# PhatStats_Slim_Enclosure_ESP_PCB_v0_96.net
KiCad netlist of a schematic drawn in EAGLE
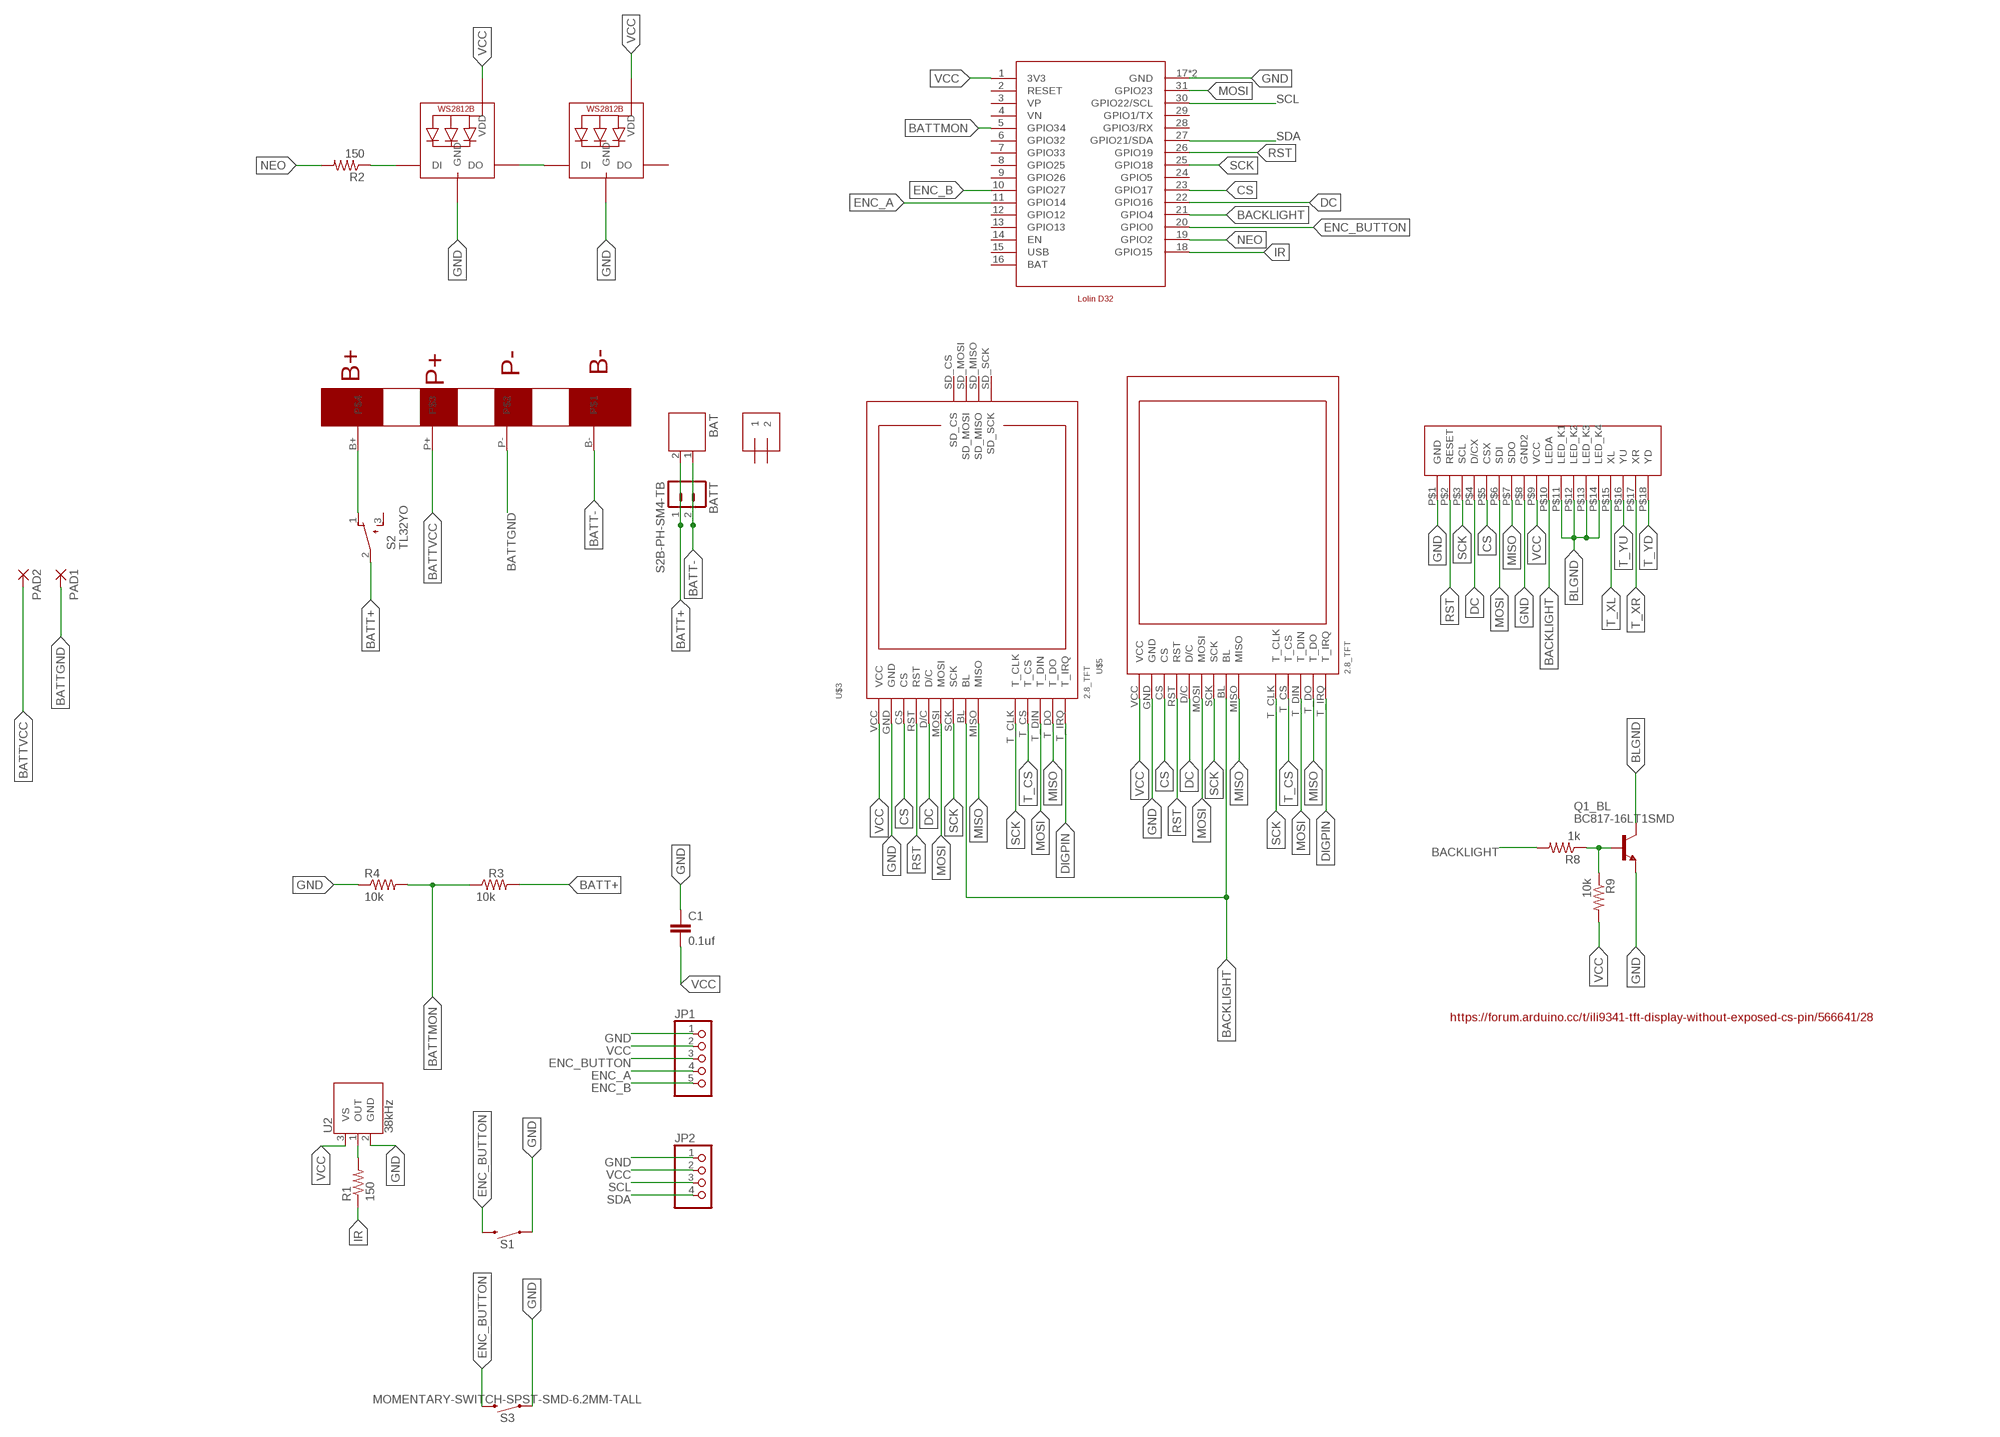
[diagram p0: schematic, sheet 1]

(export (version "E")
  (design (tool "Eeschema 10.0.6"))
  (components
    (comp (ref "0")
      (value "ILI9341-2.8")
      (footprint "eagle-import:ILI9341-2.8")
      (libsource (lib "eagle-import") (part "ILI9341-2.8"))
    )
    (comp (ref "BAT")
      (value "JST-PH2")
      (footprint "eagle-import:JST-PH2")
      (libsource (lib "eagle-import") (part "JST-PH2"))
    )
    (comp (ref "BATT")
      (value "S2B-PH-SM4-TB")
      (footprint "eagle-import:S2B-PH-SM4-TB")
      (libsource (lib "eagle-import") (part "S2B-PH-SM4-TB"))
    )
    (comp (ref "BMS")
      (value "DW01BATTERYPROT")
      (footprint "eagle-import:DW01BATTERYPROT")
      (libsource (lib "eagle-import") (part "DW01BATTERYPROT"))
    )
    (comp (ref "C1")
      (value "0.1uf")
      (footprint "eagle-import:C1206")
      (libsource (lib "eagle-import") (part "C-EUC1206"))
    )
    (comp (ref "J1")
      (value "1X2-3.5MM")
      (footprint "eagle-import:1X2-3.5MM")
      (libsource (lib "eagle-import") (part "1X2-3.5MM"))
    )
    (comp (ref "JP1")
      (value "PINHD-1X5")
      (footprint "eagle-import:1X05")
      (libsource (lib "eagle-import") (part "PINHD-1X5"))
    )
    (comp (ref "JP2")
      (value "PINHD-1X4")
      (footprint "eagle-import:1X04")
      (libsource (lib "eagle-import") (part "PINHD-1X4"))
    )
    (comp (ref "NEO1")
      (value "WS2812B5050")
      (footprint "eagle-import:WS2812B")
      (libsource (lib "eagle-import") (part "WS2812B5050"))
    )
    (comp (ref "NEO2")
      (value "WS2812B5050")
      (footprint "eagle-import:WS2812B")
      (libsource (lib "eagle-import") (part "WS2812B5050"))
    )
    (comp (ref "PAD1")
      (value "WIREPADSMD5-1,8")
      (footprint "eagle-import:5-1,8")
      (libsource (lib "eagle-import") (part "WIREPADSMD5-1,8"))
    )
    (comp (ref "PAD2")
      (value "WIREPADSMD5-1,8")
      (footprint "eagle-import:5-1,8")
      (libsource (lib "eagle-import") (part "WIREPADSMD5-1,8"))
    )
    (comp (ref "Q1_BL")
      (value "BC817-16LT1SMD")
      (footprint "eagle-import:SOT23-BEC")
      (libsource (lib "eagle-import") (part "BC817SMD-16LT1"))
    )
    (comp (ref "R1")
      (value "150")
      (footprint "eagle-import:M1206")
      (libsource (lib "eagle-import") (part "R-US_M1206"))
    )
    (comp (ref "R2")
      (value "150")
      (footprint "eagle-import:M1206")
      (libsource (lib "eagle-import") (part "R-US_M1206"))
    )
    (comp (ref "R3")
      (value "10k")
      (footprint "eagle-import:M1206")
      (libsource (lib "eagle-import") (part "R-US_M1206"))
    )
    (comp (ref "R4")
      (value "10k")
      (footprint "eagle-import:M1206")
      (libsource (lib "eagle-import") (part "R-US_M1206"))
    )
    (comp (ref "R8")
      (value "1k")
      (footprint "eagle-import:M1206")
      (libsource (lib "eagle-import") (part "R-US_M1206"))
    )
    (comp (ref "R9")
      (value "10k")
      (footprint "eagle-import:M1206")
      (libsource (lib "eagle-import") (part "R-US_M1206"))
    )
    (comp (ref "S1")
      (value "MOMENTARY-SWITCH-SPST-PTH-6.0MM")
      (footprint "eagle-import:TACTILE_SWITCH_PTH_6.0MM")
      (libsource (lib "eagle-import") (part "MOMENTARY-SWITCH-SPST-PTH-6.0MM"))
    )
    (comp (ref "S2")
      (value "TL32YO")
      (footprint "eagle-import:TL3XYO")
      (libsource (lib "eagle-import") (part "TL32YO"))
    )
    (comp (ref "S3")
      (value "MOMENTARY-SWITCH-SPST-SMD-6.2MM-TALL")
      (footprint "eagle-import:TACTILE_SWITCH_SMD_6.2MM_TALL")
      (libsource (lib "eagle-import") (part "MOMENTARY-SWITCH-SPST-SMD-6.2MM-TALL"))
    )
    (comp (ref "U$2")
      (value "LOLIND32")
      (footprint "eagle-import:LOLIND32")
      (libsource (lib "eagle-import") (part "LOLIND32"))
    )
    (comp (ref "U$3")
      (value "2.8_TFT")
      (footprint "eagle-import:2.8_TFT")
      (libsource (lib "eagle-import") (part "2.8_TFT"))
    )
    (comp (ref "U$5")
      (value "2.8_TFT")
      (footprint "eagle-import:2.8_TFT")
      (libsource (lib "eagle-import") (part "TML_ili9341-2.8_tft-display_PinHeader only_2.8_TFT"))
    )
    (comp (ref "U2")
      (value "38kHz")
      (footprint "eagle-import:TSOP382")
      (libsource (lib "eagle-import") (part "TSOP38238"))
    )
  )
  (nets
    (net (code "1") (name "/BAT") (class "Default")
      (node (ref "U$2") (pin "16") (pinfunction "BAT_16") (pintype "power_in"))
    )
    (net (code "2") (name "/SCL") (class "Default")
      (node (ref "JP2") (pin "3") (pinfunction "3_3") (pintype "passive"))
      (node (ref "U$2") (pin "30") (pinfunction "GPIO22/SCL_30") (pintype "bidirectional"))
    )
    (net (code "3") (name "/SDA") (class "Default")
      (node (ref "JP2") (pin "4") (pinfunction "4_4") (pintype "passive"))
      (node (ref "U$2") (pin "27") (pinfunction "GPIO21/SDA_27") (pintype "bidirectional"))
    )
    (net (code "4") (name "/USB") (class "Default")
      (node (ref "U$2") (pin "15") (pinfunction "USB_15") (pintype "power_in"))
    )
    (net (code "5") (name "BACKLIGHT") (class "Default")
      (node (ref "0") (pin "P$10") (pinfunction "LEDA_P$10") (pintype "bidirectional"))
      (node (ref "R8") (pin "2") (pinfunction "2_2") (pintype "passive"))
      (node (ref "U$2") (pin "21") (pinfunction "GPIO4_21") (pintype "bidirectional"))
      (node (ref "U$3") (pin "BL") (pinfunction "BL_BL") (pintype "bidirectional"))
      (node (ref "U$5") (pin "BL") (pinfunction "BL_BL") (pintype "bidirectional"))
    )
    (net (code "6") (name "BATT+") (class "Default")
      (node (ref "BAT") (pin "2") (pinfunction "2_2") (pintype "passive"))
      (node (ref "BATT") (pin "1") (pinfunction "1_1") (pintype "passive"))
      (node (ref "R3") (pin "2") (pinfunction "2_2") (pintype "passive"))
      (node (ref "S2") (pin "2") (pinfunction "P_2") (pintype "passive"))
    )
    (net (code "7") (name "BATT-") (class "Default")
      (node (ref "BAT") (pin "1") (pinfunction "1_1") (pintype "passive"))
      (node (ref "BATT") (pin "2") (pinfunction "2_2") (pintype "passive"))
      (node (ref "BMS") (pin "B-") (pinfunction "P$1_B-") (pintype "bidirectional"))
    )
    (net (code "8") (name "BATTGND") (class "Default")
      (node (ref "BMS") (pin "P-") (pinfunction "P$2_P-") (pintype "bidirectional"))
      (node (ref "PAD1") (pin "1") (pinfunction "P_1") (pintype "passive"))
    )
    (net (code "9") (name "BATTMON") (class "Default")
      (node (ref "R3") (pin "1") (pinfunction "1_1") (pintype "passive"))
      (node (ref "R4") (pin "2") (pinfunction "2_2") (pintype "passive"))
      (node (ref "U$2") (pin "5") (pinfunction "GPIO34_5") (pintype "input"))
    )
    (net (code "10") (name "BATTVCC") (class "Default")
      (node (ref "BMS") (pin "P+") (pinfunction "P$3_P+") (pintype "bidirectional"))
      (node (ref "PAD2") (pin "1") (pinfunction "P_1") (pintype "passive"))
    )
    (net (code "11") (name "BLGND") (class "Default")
      (node (ref "0") (pin "P$11") (pinfunction "LED_K1_P$11") (pintype "bidirectional"))
      (node (ref "0") (pin "P$12") (pinfunction "LED_K2_P$12") (pintype "bidirectional"))
      (node (ref "0") (pin "P$13") (pinfunction "LED_K3_P$13") (pintype "bidirectional"))
      (node (ref "0") (pin "P$14") (pinfunction "LED_K4_P$14") (pintype "bidirectional"))
      (node (ref "Q1_BL") (pin "C") (pinfunction "C_C") (pintype "passive"))
    )
    (net (code "12") (name "CS") (class "Default")
      (node (ref "0") (pin "P$5") (pinfunction "CSX_P$5") (pintype "bidirectional"))
      (node (ref "U$2") (pin "23") (pinfunction "GPIO17_23") (pintype "bidirectional"))
      (node (ref "U$3") (pin "CS") (pinfunction "CS_CS") (pintype "bidirectional"))
      (node (ref "U$5") (pin "CS") (pinfunction "CS_CS") (pintype "bidirectional"))
    )
    (net (code "13") (name "DC") (class "Default")
      (node (ref "0") (pin "P$4") (pinfunction "D/CX_P$4") (pintype "bidirectional"))
      (node (ref "U$2") (pin "22") (pinfunction "GPIO16_22") (pintype "bidirectional"))
      (node (ref "U$3") (pin "D/C") (pinfunction "D/C_D/C") (pintype "bidirectional"))
      (node (ref "U$5") (pin "D/C") (pinfunction "D/C_D/C") (pintype "bidirectional"))
    )
    (net (code "14") (name "DIGPIN") (class "Default")
      (node (ref "U$3") (pin "T_IRQ") (pinfunction "T_IRQ_T_IRQ") (pintype "bidirectional"))
      (node (ref "U$5") (pin "T_IRQ") (pinfunction "T_IRQ_T_IRQ") (pintype "bidirectional"))
    )
    (net (code "15") (name "ENC_A") (class "Default")
      (node (ref "JP1") (pin "4") (pinfunction "4_4") (pintype "passive"))
      (node (ref "U$2") (pin "11") (pinfunction "GPIO14_11") (pintype "bidirectional"))
    )
    (net (code "16") (name "ENC_B") (class "Default")
      (node (ref "JP1") (pin "5") (pinfunction "5_5") (pintype "passive"))
      (node (ref "U$2") (pin "10") (pinfunction "GPIO27_10") (pintype "bidirectional"))
    )
    (net (code "17") (name "ENC_BUTTON") (class "Default")
      (node (ref "JP1") (pin "3") (pinfunction "3_3") (pintype "passive"))
      (node (ref "S1") (pin "3") (pinfunction "2_3") (pintype "passive"))
      (node (ref "S3") (pin "B2") (pinfunction "2_B2") (pintype "passive"))
      (node (ref "U$2") (pin "20") (pinfunction "GPIO0_20") (pintype "bidirectional"))
    )
    (net (code "18") (name "GND") (class "Default")
      (node (ref "0") (pin "P$1") (pinfunction "GND_P$1") (pintype "bidirectional"))
      (node (ref "0") (pin "P$8") (pinfunction "GND2_P$8") (pintype "bidirectional"))
      (node (ref "C1") (pin "1") (pinfunction "1_1") (pintype "passive"))
      (node (ref "JP1") (pin "1") (pinfunction "1_1") (pintype "passive"))
      (node (ref "JP2") (pin "1") (pinfunction "1_1") (pintype "passive"))
      (node (ref "NEO1") (pin "3-GND") (pinfunction "GND_3-GND") (pintype "power_in"))
      (node (ref "NEO2") (pin "3-GND") (pinfunction "GND_3-GND") (pintype "power_in"))
      (node (ref "Q1_BL") (pin "E") (pinfunction "E_E") (pintype "passive"))
      (node (ref "R4") (pin "1") (pinfunction "1_1") (pintype "passive"))
      (node (ref "S1") (pin "1") (pinfunction "1_1") (pintype "passive"))
      (node (ref "S3") (pin "A2") (pinfunction "1_A2") (pintype "passive"))
      (node (ref "U$2") (pin "17") (pinfunction "GND_17") (pintype "power_in"))
      (node (ref "U$2") (pin "32") (pinfunction "GND_32") (pintype "power_in"))
      (node (ref "U$3") (pin "GND") (pinfunction "GND_GND") (pintype "bidirectional"))
      (node (ref "U$5") (pin "GND") (pinfunction "GND_GND") (pintype "bidirectional"))
      (node (ref "U2") (pin "2") (pinfunction "GND_2") (pintype "bidirectional"))
    )
    (net (code "19") (name "IR") (class "Default")
      (node (ref "R1") (pin "1") (pinfunction "1_1") (pintype "passive"))
      (node (ref "U$2") (pin "18") (pinfunction "GPIO15_18") (pintype "bidirectional"))
    )
    (net (code "20") (name "MISO") (class "Default")
      (node (ref "0") (pin "P$7") (pinfunction "SDO_P$7") (pintype "bidirectional"))
      (node (ref "U$3") (pin "MISO") (pinfunction "MISO_MISO") (pintype "bidirectional"))
      (node (ref "U$3") (pin "T_DO") (pinfunction "T_DO_T_DO") (pintype "bidirectional"))
      (node (ref "U$5") (pin "MISO") (pinfunction "MISO_MISO") (pintype "bidirectional"))
      (node (ref "U$5") (pin "T_DO") (pinfunction "T_DO_T_DO") (pintype "bidirectional"))
    )
    (net (code "21") (name "MOSI") (class "Default")
      (node (ref "0") (pin "P$6") (pinfunction "SDI_P$6") (pintype "bidirectional"))
      (node (ref "U$2") (pin "31") (pinfunction "GPIO23_31") (pintype "bidirectional"))
      (node (ref "U$3") (pin "MOSI") (pinfunction "MOSI_MOSI") (pintype "bidirectional"))
      (node (ref "U$3") (pin "T_DIN") (pinfunction "T_DIN_T_DIN") (pintype "bidirectional"))
      (node (ref "U$5") (pin "MOSI") (pinfunction "MOSI_MOSI") (pintype "bidirectional"))
      (node (ref "U$5") (pin "T_DIN") (pinfunction "T_DIN_T_DIN") (pintype "bidirectional"))
    )
    (net (code "22") (name "NEO") (class "Default")
      (node (ref "R2") (pin "2") (pinfunction "2_2") (pintype "passive"))
      (node (ref "U$2") (pin "19") (pinfunction "GPIO2_19") (pintype "bidirectional"))
    )
    (net (code "23") (name "Net-(BMS-P$4)") (class "Default")
      (node (ref "BMS") (pin "B+") (pinfunction "P$4_B+") (pintype "bidirectional"))
      (node (ref "S2") (pin "1") (pinfunction "O_1") (pintype "passive"))
    )
    (net (code "24") (name "Net-(NEO1-DI)") (class "Default")
      (node (ref "NEO1") (pin "4-DIN") (pinfunction "DI_4-DIN") (pintype "input"))
      (node (ref "R2") (pin "1") (pinfunction "1_1") (pintype "passive"))
    )
    (net (code "25") (name "Net-(NEO1-DO)") (class "Default")
      (node (ref "NEO1") (pin "2-DOUT") (pinfunction "DO_2-DOUT") (pintype "output"))
      (node (ref "NEO2") (pin "4-DIN") (pinfunction "DI_4-DIN") (pintype "input"))
    )
    (net (code "26") (name "Net-(Q1_BL-PadB)") (class "Default")
      (node (ref "Q1_BL") (pin "B") (pinfunction "B_B") (pintype "passive"))
      (node (ref "R8") (pin "1") (pinfunction "1_1") (pintype "passive"))
      (node (ref "R9") (pin "1") (pinfunction "1_1") (pintype "passive"))
    )
    (net (code "27") (name "Net-(U2-OUT)") (class "Default")
      (node (ref "R1") (pin "2") (pinfunction "2_2") (pintype "passive"))
      (node (ref "U2") (pin "1") (pinfunction "OUT_1") (pintype "bidirectional"))
    )
    (net (code "28") (name "RST") (class "Default")
      (node (ref "0") (pin "P$2") (pinfunction "RESET_P$2") (pintype "bidirectional"))
      (node (ref "U$2") (pin "26") (pinfunction "GPIO19_26") (pintype "bidirectional"))
      (node (ref "U$3") (pin "RST") (pinfunction "RST_RST") (pintype "bidirectional"))
      (node (ref "U$5") (pin "RST") (pinfunction "RST_RST") (pintype "bidirectional"))
    )
    (net (code "29") (name "SCK") (class "Default")
      (node (ref "0") (pin "P$3") (pinfunction "SCL_P$3") (pintype "bidirectional"))
      (node (ref "U$2") (pin "25") (pinfunction "GPIO18_25") (pintype "bidirectional"))
      (node (ref "U$3") (pin "SCK") (pinfunction "SCK_SCK") (pintype "bidirectional"))
      (node (ref "U$3") (pin "T_CLK") (pinfunction "T_CLK_T_CLK") (pintype "bidirectional"))
      (node (ref "U$5") (pin "SCK") (pinfunction "SCK_SCK") (pintype "bidirectional"))
      (node (ref "U$5") (pin "T_CLK") (pinfunction "T_CLK_T_CLK") (pintype "bidirectional"))
    )
    (net (code "30") (name "T_CS") (class "Default")
      (node (ref "U$3") (pin "T_CS") (pinfunction "T_CS_T_CS") (pintype "bidirectional"))
      (node (ref "U$5") (pin "T_CS") (pinfunction "T_CS_T_CS") (pintype "bidirectional"))
    )
    (net (code "31") (name "T_XL") (class "Default")
      (node (ref "0") (pin "P$15") (pinfunction "XL_P$15") (pintype "bidirectional"))
    )
    (net (code "32") (name "T_XR") (class "Default")
      (node (ref "0") (pin "P$17") (pinfunction "XR_P$17") (pintype "bidirectional"))
    )
    (net (code "33") (name "T_YD") (class "Default")
      (node (ref "0") (pin "P$18") (pinfunction "YD_P$18") (pintype "bidirectional"))
    )
    (net (code "34") (name "T_YU") (class "Default")
      (node (ref "0") (pin "P$16") (pinfunction "YU_P$16") (pintype "bidirectional"))
    )
    (net (code "35") (name "VCC") (class "Default")
      (node (ref "0") (pin "P$9") (pinfunction "VCC_P$9") (pintype "bidirectional"))
      (node (ref "C1") (pin "2") (pinfunction "2_2") (pintype "passive"))
      (node (ref "JP1") (pin "2") (pinfunction "2_2") (pintype "passive"))
      (node (ref "JP2") (pin "2") (pinfunction "2_2") (pintype "passive"))
      (node (ref "NEO1") (pin "1-VDD") (pinfunction "VDD_1-VDD") (pintype "power_in"))
      (node (ref "NEO2") (pin "1-VDD") (pinfunction "VDD_1-VDD") (pintype "power_in"))
      (node (ref "R9") (pin "2") (pinfunction "2_2") (pintype "passive"))
      (node (ref "U$2") (pin "1") (pinfunction "3V3_1") (pintype "power_in"))
      (node (ref "U$3") (pin "VCC") (pinfunction "VCC_VCC") (pintype "bidirectional"))
      (node (ref "U$5") (pin "VCC") (pinfunction "VCC_VCC") (pintype "bidirectional"))
      (node (ref "U2") (pin "3") (pinfunction "VS_3") (pintype "bidirectional"))
    )
    (net (code "36") (name "unconnected-(J1-Pad1)") (class "Default")
      (node (ref "J1") (pin "1") (pinfunction "1_1") (pintype "passive"))
    )
    (net (code "37") (name "unconnected-(J1-Pad2)") (class "Default")
      (node (ref "J1") (pin "2") (pinfunction "2_2") (pintype "passive"))
    )
    (net (code "38") (name "unconnected-(NEO2-DO-Pad2-DOUT)") (class "Default")
      (node (ref "NEO2") (pin "2-DOUT") (pinfunction "DO_2-DOUT") (pintype "output"))
    )
    (net (code "39") (name "unconnected-(S2-S-Pad3)") (class "Default")
      (node (ref "S2") (pin "3") (pinfunction "S_3") (pintype "passive"))
    )
    (net (code "40") (name "unconnected-(U$2-EN-Pad14)") (class "Default")
      (node (ref "U$2") (pin "14") (pinfunction "EN_14") (pintype "input"))
    )
    (net (code "41") (name "unconnected-(U$2-GPIO1{slash}TX-Pad29)") (class "Default")
      (node (ref "U$2") (pin "29") (pinfunction "GPIO1/TX_29") (pintype "bidirectional"))
    )
    (net (code "42") (name "unconnected-(U$2-GPIO3{slash}RX-Pad28)") (class "Default")
      (node (ref "U$2") (pin "28") (pinfunction "GPIO3/RX_28") (pintype "bidirectional"))
    )
    (net (code "43") (name "unconnected-(U$2-GPIO5-Pad24)") (class "Default")
      (node (ref "U$2") (pin "24") (pinfunction "GPIO5_24") (pintype "bidirectional"))
    )
    (net (code "44") (name "unconnected-(U$2-GPIO12-Pad12)") (class "Default")
      (node (ref "U$2") (pin "12") (pinfunction "GPIO12_12") (pintype "bidirectional"))
    )
    (net (code "45") (name "unconnected-(U$2-GPIO13-Pad13)") (class "Default")
      (node (ref "U$2") (pin "13") (pinfunction "GPIO13_13") (pintype "bidirectional"))
    )
    (net (code "46") (name "unconnected-(U$2-GPIO25-Pad8)") (class "Default")
      (node (ref "U$2") (pin "8") (pinfunction "GPIO25_8") (pintype "bidirectional"))
    )
    (net (code "47") (name "unconnected-(U$2-GPIO26-Pad9)") (class "Default")
      (node (ref "U$2") (pin "9") (pinfunction "GPIO26_9") (pintype "bidirectional"))
    )
    (net (code "48") (name "unconnected-(U$2-GPIO32-Pad6)") (class "Default")
      (node (ref "U$2") (pin "6") (pinfunction "GPIO32_6") (pintype "bidirectional"))
    )
    (net (code "49") (name "unconnected-(U$2-GPIO33-Pad7)") (class "Default")
      (node (ref "U$2") (pin "7") (pinfunction "GPIO33_7") (pintype "bidirectional"))
    )
    (net (code "50") (name "unconnected-(U$2-RESET-Pad2)") (class "Default")
      (node (ref "U$2") (pin "2") (pinfunction "RESET_2") (pintype "input"))
    )
    (net (code "51") (name "unconnected-(U$2-VN-Pad4)") (class "Default")
      (node (ref "U$2") (pin "4") (pinfunction "VN_4") (pintype "no_connect"))
    )
    (net (code "52") (name "unconnected-(U$2-VP-Pad3)") (class "Default")
      (node (ref "U$2") (pin "3") (pinfunction "VP_3") (pintype "no_connect"))
    )
    (net (code "53") (name "unconnected-(U$3-PadSD_CS)") (class "Default")
      (node (ref "U$3") (pin "SD_CS") (pinfunction "SD_CS_SD_CS") (pintype "bidirectional"))
    )
    (net (code "54") (name "unconnected-(U$3-PadSD_MISO)") (class "Default")
      (node (ref "U$3") (pin "SD_MISO") (pinfunction "SD_MISO_SD_MISO") (pintype "bidirectional"))
    )
    (net (code "55") (name "unconnected-(U$3-PadSD_MOSI)") (class "Default")
      (node (ref "U$3") (pin "SD_MOSI") (pinfunction "SD_MOSI_SD_MOSI") (pintype "bidirectional"))
    )
    (net (code "56") (name "unconnected-(U$3-PadSD_SCK)") (class "Default")
      (node (ref "U$3") (pin "SD_SCK") (pinfunction "SD_SCK_SD_SCK") (pintype "bidirectional"))
    )
  )
)
